# ControlBoard.net
KiCad netlist of a schematic drawn in Altium Designer
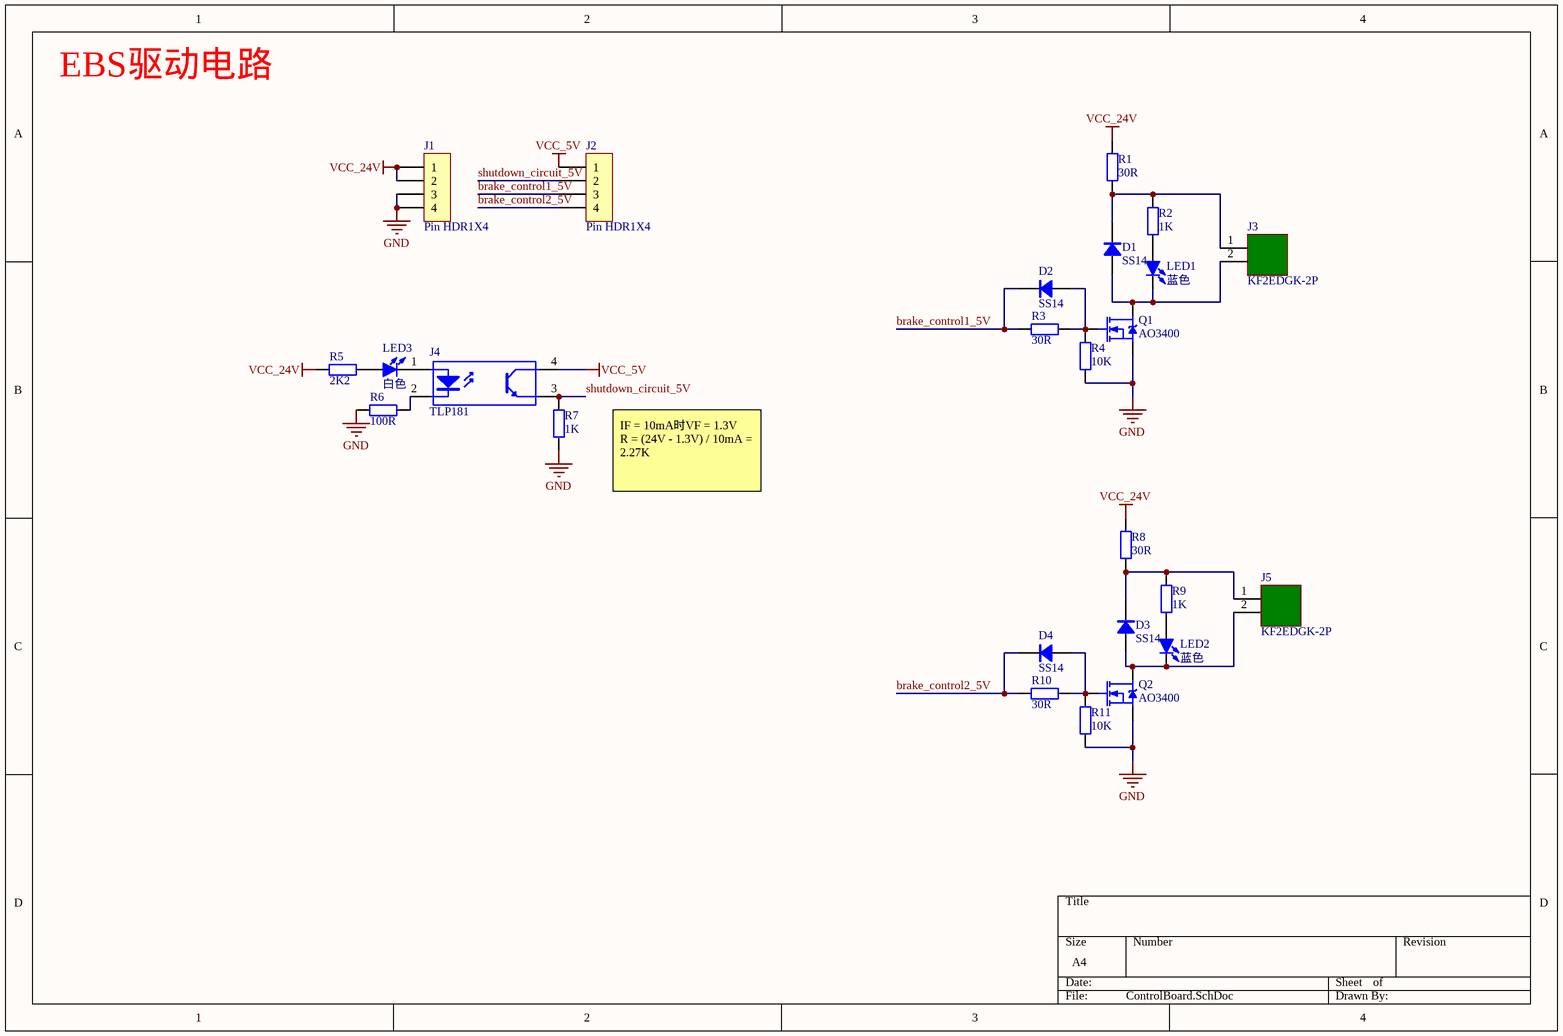
[diagram p0: ControlBoard.SchDoc]

(export (version "E")
  (design (tool "Eeschema 10.0.6"))
  (components
    (comp (ref "D1")
      (value "SS14")
      (footprint "SMA")
      (description "肖特基二极管")
      (fields (field (name "版权归属") "源创客"))
      (libsource (lib "mainlib") (part "SS14"))
    )
    (comp (ref "D2")
      (value "SS14")
      (footprint "SMA")
      (description "肖特基二极管")
      (fields (field (name "版权归属") "源创客"))
      (libsource (lib "mainlib") (part "SS14"))
    )
    (comp (ref "D3")
      (value "SS14")
      (footprint "SMA")
      (description "肖特基二极管")
      (fields (field (name "版权归属") "源创客"))
      (libsource (lib "mainlib") (part "SS14"))
    )
    (comp (ref "D4")
      (value "SS14")
      (footprint "SMA")
      (description "肖特基二极管")
      (fields (field (name "版权归属") "源创客"))
      (libsource (lib "mainlib") (part "SS14"))
    )
    (comp (ref "J1")
      (value "Pin HDR1X4")
      (footprint "Pin HDR1X4/2.54mm-S")
      (libsource (lib "mainlib") (part "Pin HDR1X4"))
    )
    (comp (ref "J2")
      (value "Pin HDR1X4")
      (footprint "Pin HDR1X4/2.54mm-S")
      (libsource (lib "mainlib") (part "Pin HDR1X4"))
    )
    (comp (ref "J3")
      (value "KF2EDGK-2P")
      (footprint "KF2EDGK5.08W-2P")
      (libsource (lib "mainlib") (part "KF2EDGK-2P"))
    )
    (comp (ref "J4")
      (value "TLP181")
      (footprint "SOP4")
      (description "光耦")
      (fields (field (name "版权归属") "源创客"))
      (libsource (lib "mainlib") (part "TLP181"))
    )
    (comp (ref "J5")
      (value "KF2EDGK-2P")
      (footprint "KF2EDGK5.08W-2P")
      (libsource (lib "mainlib") (part "KF2EDGK-2P"))
    )
    (comp (ref "LED1")
      (value "蓝色")
      (footprint "LED 0805B")
      (description "贴片LED")
      (fields (field (name "版权归属") "源创客"))
      (libsource (lib "mainlib") (part "LED-SMD"))
    )
    (comp (ref "LED2")
      (value "蓝色")
      (footprint "LED 0805B")
      (description "贴片LED")
      (fields (field (name "版权归属") "源创客"))
      (libsource (lib "mainlib") (part "LED-SMD"))
    )
    (comp (ref "LED3")
      (value "白色")
      (footprint "LED 0805W")
      (description "贴片LED")
      (fields (field (name "版权归属") "源创客"))
      (libsource (lib "mainlib") (part "LED-SMD"))
    )
    (comp (ref "Q1")
      (value "AO3400")
      (footprint "SOT23")
      (description "N沟道场效应管")
      (libsource (lib "mainlib") (part "N-MOS"))
    )
    (comp (ref "Q2")
      (value "AO3400")
      (footprint "SOT23")
      (description "N沟道场效应管")
      (libsource (lib "mainlib") (part "N-MOS"))
    )
    (comp (ref "R1")
      (value "30R")
      (footprint "0805R")
      (description "贴片电阻")
      (libsource (lib "mainlib") (part "RES"))
    )
    (comp (ref "R2")
      (value "1K")
      (footprint "0805R")
      (description "贴片电阻")
      (libsource (lib "mainlib") (part "RES"))
    )
    (comp (ref "R3")
      (value "30R")
      (footprint "0805R")
      (description "贴片电阻")
      (libsource (lib "") (part "RES_1"))
    )
    (comp (ref "R4")
      (value "10K")
      (footprint "0805R")
      (description "贴片电阻")
      (libsource (lib "mainlib") (part "RES"))
    )
    (comp (ref "R5")
      (value "2K2")
      (footprint "0805R")
      (description "贴片电阻")
      (libsource (lib "") (part "RES_1"))
    )
    (comp (ref "R6")
      (value "100R")
      (footprint "0805R")
      (description "贴片电阻")
      (libsource (lib "") (part "RES_1"))
    )
    (comp (ref "R7")
      (value "1K")
      (footprint "0805R")
      (description "贴片电阻")
      (libsource (lib "mainlib") (part "RES"))
    )
    (comp (ref "R8")
      (value "30R")
      (footprint "0805R")
      (description "贴片电阻")
      (libsource (lib "mainlib") (part "RES"))
    )
    (comp (ref "R9")
      (value "1K")
      (footprint "0805R")
      (description "贴片电阻")
      (libsource (lib "mainlib") (part "RES"))
    )
    (comp (ref "R10")
      (value "30R")
      (footprint "0805R")
      (description "贴片电阻")
      (libsource (lib "") (part "RES_1"))
    )
    (comp (ref "R11")
      (value "10K")
      (footprint "0805R")
      (description "贴片电阻")
      (libsource (lib "mainlib") (part "RES"))
    )
  )
  (nets
    (net (code "1") (name "/brake_control1_5V") (class "Default")
      (node (ref "D2") (pin "2") (pinfunction "K_2") (pintype "passive"))
      (node (ref "J2") (pin "3") (pinfunction "3_3") (pintype "passive"))
      (node (ref "R3") (pin "2") (pinfunction "2_2") (pintype "passive"))
    )
    (net (code "2") (name "/brake_control2_5V") (class "Default")
      (node (ref "D4") (pin "2") (pinfunction "K_2") (pintype "passive"))
      (node (ref "J2") (pin "4") (pinfunction "4_4") (pintype "passive"))
      (node (ref "R10") (pin "2") (pinfunction "2_2") (pintype "passive"))
    )
    (net (code "3") (name "/shutdown_circuit_5V") (class "Default")
      (node (ref "J2") (pin "2") (pinfunction "2_2") (pintype "passive"))
      (node (ref "J4") (pin "3") (pinfunction "E_3") (pintype "passive"))
      (node (ref "R7") (pin "1") (pinfunction "1_1") (pintype "passive"))
    )
    (net (code "4") (name "GND") (class "Default")
      (node (ref "J1") (pin "3") (pinfunction "3_3") (pintype "passive"))
      (node (ref "J1") (pin "4") (pinfunction "4_4") (pintype "passive"))
      (node (ref "Q1") (pin "S") (pinfunction "S_S") (pintype "passive"))
      (node (ref "Q2") (pin "S") (pinfunction "S_S") (pintype "passive"))
      (node (ref "R11") (pin "2") (pinfunction "2_2") (pintype "passive"))
      (node (ref "R4") (pin "2") (pinfunction "2_2") (pintype "passive"))
      (node (ref "R6") (pin "2") (pinfunction "2_2") (pintype "passive"))
      (node (ref "R7") (pin "2") (pinfunction "2_2") (pintype "passive"))
    )
    (net (code "5") (name "Net-(D1-A)") (class "Default")
      (node (ref "D1") (pin "1") (pinfunction "A_1") (pintype "passive"))
      (node (ref "J3") (pin "2") (pinfunction "2_2") (pintype "passive"))
      (node (ref "LED1") (pin "2") (pinfunction "K_2") (pintype "passive"))
      (node (ref "Q1") (pin "D") (pinfunction "D_D") (pintype "passive"))
    )
    (net (code "6") (name "Net-(D1-K)") (class "Default")
      (node (ref "D1") (pin "2") (pinfunction "K_2") (pintype "passive"))
      (node (ref "J3") (pin "1") (pinfunction "1_1") (pintype "passive"))
      (node (ref "R1") (pin "2") (pinfunction "2_2") (pintype "passive"))
      (node (ref "R2") (pin "1") (pinfunction "1_1") (pintype "passive"))
    )
    (net (code "7") (name "Net-(D2-A)") (class "Default")
      (node (ref "D2") (pin "1") (pinfunction "A_1") (pintype "passive"))
      (node (ref "Q1") (pin "G") (pinfunction "G_G") (pintype "passive"))
      (node (ref "R3") (pin "1") (pinfunction "1_1") (pintype "passive"))
      (node (ref "R4") (pin "1") (pinfunction "1_1") (pintype "passive"))
    )
    (net (code "8") (name "Net-(D3-A)") (class "Default")
      (node (ref "D3") (pin "1") (pinfunction "A_1") (pintype "passive"))
      (node (ref "J5") (pin "2") (pinfunction "2_2") (pintype "passive"))
      (node (ref "LED2") (pin "2") (pinfunction "K_2") (pintype "passive"))
      (node (ref "Q2") (pin "D") (pinfunction "D_D") (pintype "passive"))
    )
    (net (code "9") (name "Net-(D3-K)") (class "Default")
      (node (ref "D3") (pin "2") (pinfunction "K_2") (pintype "passive"))
      (node (ref "J5") (pin "1") (pinfunction "1_1") (pintype "passive"))
      (node (ref "R8") (pin "2") (pinfunction "2_2") (pintype "passive"))
      (node (ref "R9") (pin "1") (pinfunction "1_1") (pintype "passive"))
    )
    (net (code "10") (name "Net-(D4-A)") (class "Default")
      (node (ref "D4") (pin "1") (pinfunction "A_1") (pintype "passive"))
      (node (ref "Q2") (pin "G") (pinfunction "G_G") (pintype "passive"))
      (node (ref "R10") (pin "1") (pinfunction "1_1") (pintype "passive"))
      (node (ref "R11") (pin "1") (pinfunction "1_1") (pintype "passive"))
    )
    (net (code "11") (name "Net-(J4-A)") (class "Default")
      (node (ref "J4") (pin "1") (pinfunction "A_1") (pintype "passive"))
      (node (ref "LED3") (pin "2") (pinfunction "K_2") (pintype "passive"))
    )
    (net (code "12") (name "Net-(J4-K)") (class "Default")
      (node (ref "J4") (pin "2") (pinfunction "K_2") (pintype "passive"))
      (node (ref "R6") (pin "1") (pinfunction "1_1") (pintype "passive"))
    )
    (net (code "13") (name "Net-(LED1-A)") (class "Default")
      (node (ref "LED1") (pin "1") (pinfunction "A_1") (pintype "passive"))
      (node (ref "R2") (pin "2") (pinfunction "2_2") (pintype "passive"))
    )
    (net (code "14") (name "Net-(LED2-A)") (class "Default")
      (node (ref "LED2") (pin "1") (pinfunction "A_1") (pintype "passive"))
      (node (ref "R9") (pin "2") (pinfunction "2_2") (pintype "passive"))
    )
    (net (code "15") (name "Net-(LED3-A)") (class "Default")
      (node (ref "LED3") (pin "1") (pinfunction "A_1") (pintype "passive"))
      (node (ref "R5") (pin "1") (pinfunction "1_1") (pintype "passive"))
    )
    (net (code "16") (name "VCC_5V") (class "Default")
      (node (ref "J2") (pin "1") (pinfunction "1_1") (pintype "passive"))
      (node (ref "J4") (pin "4") (pinfunction "C_4") (pintype "passive"))
    )
    (net (code "17") (name "VCC_24V") (class "Default")
      (node (ref "J1") (pin "1") (pinfunction "1_1") (pintype "passive"))
      (node (ref "J1") (pin "2") (pinfunction "2_2") (pintype "passive"))
      (node (ref "R1") (pin "1") (pinfunction "1_1") (pintype "passive"))
      (node (ref "R5") (pin "2") (pinfunction "2_2") (pintype "passive"))
      (node (ref "R8") (pin "1") (pinfunction "1_1") (pintype "passive"))
    )
  )
)
